# EasyEDA_ATTinyX5_Programmer_V1_Schematic.net
KiCad netlist of a schematic drawn in EasyEDA
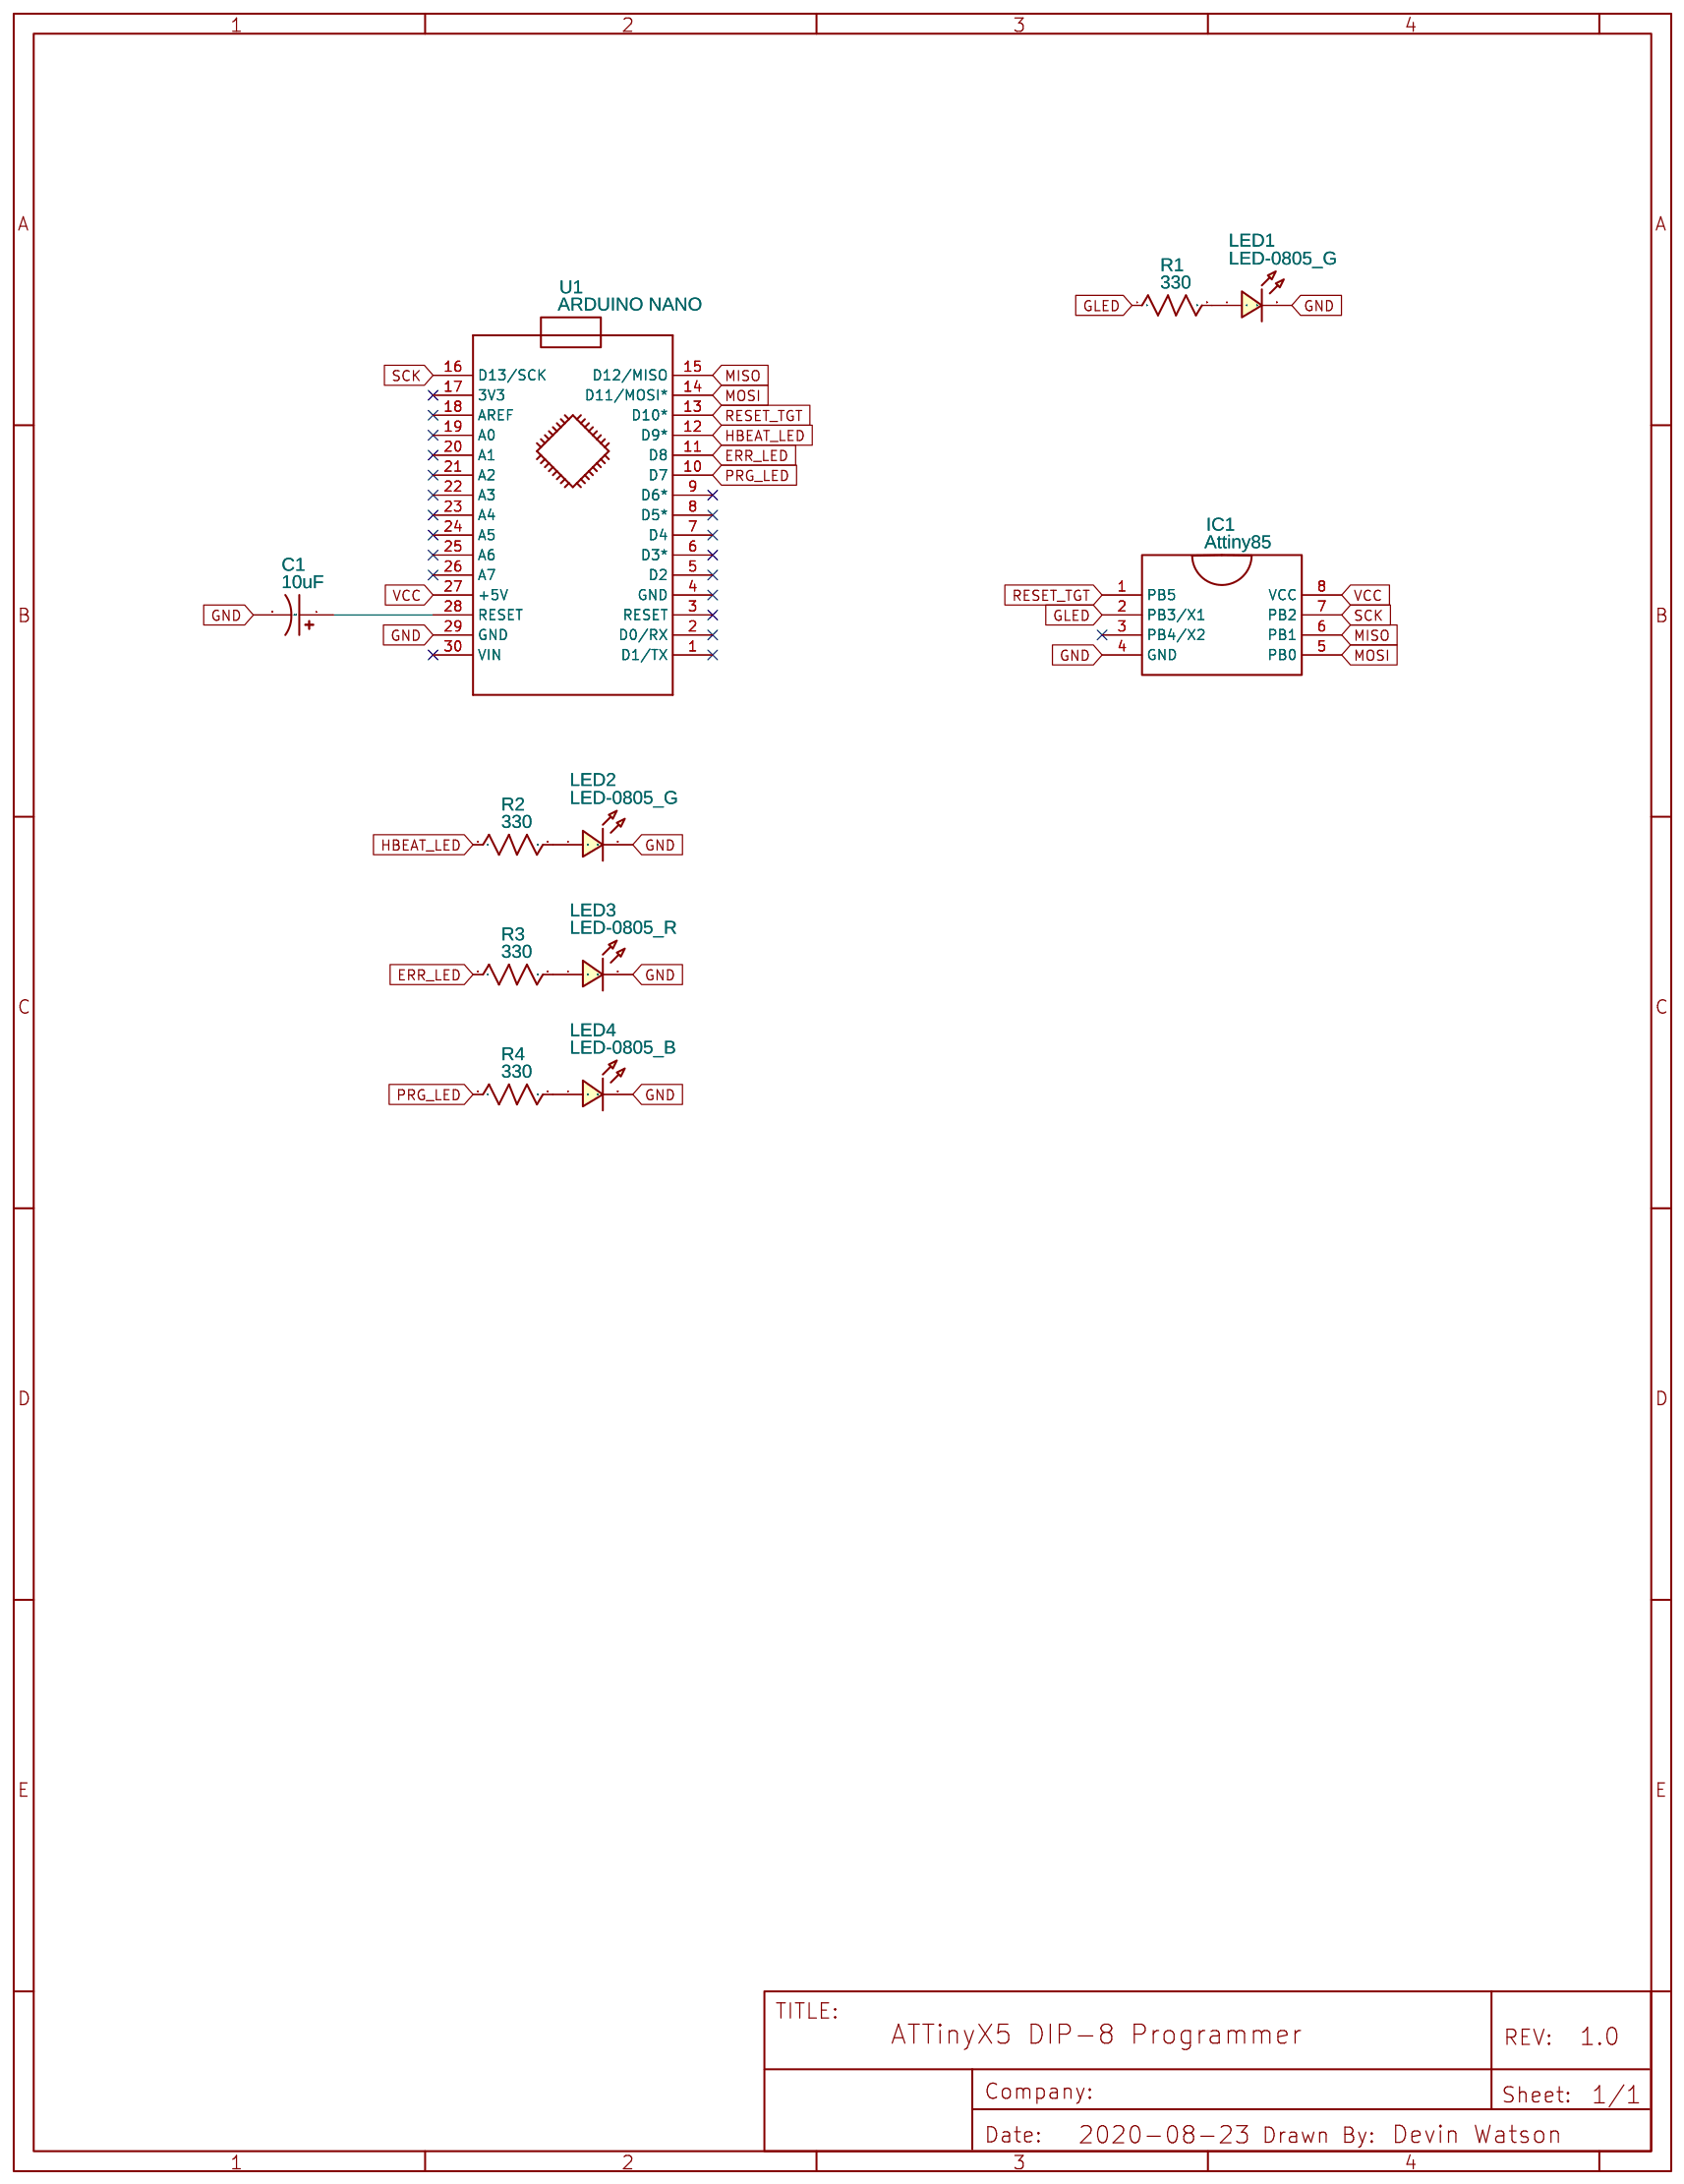
[diagram p0: schematic sheet]

(export (version "E")
  (design (tool "Eeschema 10.0.6"))
  (components
    (comp (ref "C1")
      (value "10uF")
      (fields
        (field (name "BOM_Manufacturer Part") "EEE-HP0J100R")
        (field (name "BOM_Supplier Part") "667-EEE-HP0J100R")
      )
      (libsource (lib "") (part "CE_SMD_D4.0×H5.5_US"))
    )
    (comp (ref "IC1") (value "Attiny85") (libsource (lib "") (part "Attiny85")))
    (comp (ref "LED1")
      (value "LED-0805_G")
      (fields
        (field (name "BOM_Manufacturer Part") "17-21SYGC/S530-E2/TR8")
        (field (name "BOM_Supplier Part") "638-1721SYGCS530E2")
      )
      (libsource (lib "") (part "LED-0805_G"))
    )
    (comp (ref "LED2")
      (value "LED-0805_G")
      (fields
        (field (name "BOM_Manufacturer Part") "17-21SYGC/S530-E2/TR8")
        (field (name "BOM_Supplier Part") "638-1721SYGCS530E2")
      )
      (libsource (lib "") (part "LED-0805_G"))
    )
    (comp (ref "LED3")
      (value "LED-0805_R")
      (fields
        (field (name "BOM_Manufacturer Part") "EL-12-215SURC/S530-A2/TR8")
        (field (name "BOM_Supplier Part") "638-215SURCS530A28")
      )
      (libsource (lib "") (part "LED-0805_R"))
    )
    (comp (ref "LED4")
      (value "LED-0805_B")
      (fields
        (field (name "BOM_Manufacturer Part") "LTST-C170TBKT")
        (field (name "BOM_Supplier Part") "859-LTST-C170TBKT")
      )
      (libsource (lib "") (part "LED-0805_B"))
    )
    (comp (ref "R1")
      (value "330")
      (fields
        (field (name "BOM_Manufacturer Part") "CRCW0805330RJNEAC")
        (field (name "BOM_Supplier Part") "71-CRCW0805330RJNEAC")
      )
      (libsource (lib "") (part "R_0805_US"))
    )
    (comp (ref "R2")
      (value "330")
      (fields
        (field (name "BOM_Manufacturer Part") "CRCW0805330RJNEAC")
        (field (name "BOM_Supplier Part") "71-CRCW0805330RJNEAC")
      )
      (libsource (lib "") (part "R_0805_US"))
    )
    (comp (ref "R3")
      (value "330")
      (fields
        (field (name "BOM_Manufacturer Part") "CRCW0805330RJNEAC")
        (field (name "BOM_Supplier Part") "71-CRCW0805330RJNEAC")
      )
      (libsource (lib "") (part "R_0805_US"))
    )
    (comp (ref "R4")
      (value "330")
      (fields
        (field (name "BOM_Manufacturer Part") "CRCW0805330RJNEAC")
        (field (name "BOM_Supplier Part") "71-CRCW0805330RJNEAC")
      )
      (libsource (lib "") (part "R_0805_US"))
    )
    (comp (ref "U1")
      (value "ARDUINO NANO")
      (fields (field (name "BOM_Manufacturer Part") "?"))
      (libsource (lib "") (part "Unknown_280_-560"))
    )
  )
  (nets
    (net (code "1") (name "ERR_LED") (class "Default")
      (node (ref "R3") (pin "1") (pinfunction "1_1") (pintype "unspecified"))
      (node (ref "U1") (pin "11") (pinfunction "D8_11") (pintype "unspecified"))
    )
    (net (code "2") (name "GLED") (class "Default")
      (node (ref "IC1") (pin "2") (pinfunction "PB3/X1_2") (pintype "bidirectional"))
      (node (ref "R1") (pin "1") (pinfunction "1_1") (pintype "unspecified"))
    )
    (net (code "3") (name "GND") (class "Default")
      (node (ref "C1") (pin "2") (pinfunction "2_2") (pintype "unspecified"))
      (node (ref "IC1") (pin "4") (pinfunction "GND_4") (pintype "passive"))
      (node (ref "LED1") (pin "2") (pinfunction "2_2") (pintype "unspecified"))
      (node (ref "LED2") (pin "2") (pinfunction "2_2") (pintype "unspecified"))
      (node (ref "LED3") (pin "2") (pinfunction "2_2") (pintype "unspecified"))
      (node (ref "LED4") (pin "2") (pinfunction "2_2") (pintype "unspecified"))
      (node (ref "U1") (pin "29") (pinfunction "GND_29") (pintype "unspecified"))
    )
    (net (code "4") (name "HBEAT_LED") (class "Default")
      (node (ref "R2") (pin "1") (pinfunction "1_1") (pintype "unspecified"))
      (node (ref "U1") (pin "12") (pinfunction "D9*_12") (pintype "unspecified"))
    )
    (net (code "5") (name "MISO") (class "Default")
      (node (ref "IC1") (pin "6") (pinfunction "PB1_6") (pintype "bidirectional"))
      (node (ref "U1") (pin "15") (pinfunction "D12/MISO_15") (pintype "unspecified"))
    )
    (net (code "6") (name "MOSI") (class "Default")
      (node (ref "IC1") (pin "5") (pinfunction "PB0_5") (pintype "bidirectional"))
      (node (ref "U1") (pin "14") (pinfunction "D11/MOSI*_14") (pintype "unspecified"))
    )
    (net (code "7") (name "Net-(C1-Pad1)") (class "Default")
      (node (ref "C1") (pin "1") (pinfunction "1_1") (pintype "unspecified"))
      (node (ref "U1") (pin "28") (pinfunction "RESET_28") (pintype "unspecified"))
    )
    (net (code "8") (name "Net-(LED1-Pad1)") (class "Default")
      (node (ref "LED1") (pin "1") (pinfunction "1_1") (pintype "unspecified"))
      (node (ref "R1") (pin "2") (pinfunction "2_2") (pintype "unspecified"))
    )
    (net (code "9") (name "Net-(LED2-Pad1)") (class "Default")
      (node (ref "LED2") (pin "1") (pinfunction "1_1") (pintype "unspecified"))
      (node (ref "R2") (pin "2") (pinfunction "2_2") (pintype "unspecified"))
    )
    (net (code "10") (name "Net-(LED3-Pad1)") (class "Default")
      (node (ref "LED3") (pin "1") (pinfunction "1_1") (pintype "unspecified"))
      (node (ref "R3") (pin "2") (pinfunction "2_2") (pintype "unspecified"))
    )
    (net (code "11") (name "Net-(LED4-Pad1)") (class "Default")
      (node (ref "LED4") (pin "1") (pinfunction "1_1") (pintype "unspecified"))
      (node (ref "R4") (pin "2") (pinfunction "2_2") (pintype "unspecified"))
    )
    (net (code "12") (name "PRG_LED") (class "Default")
      (node (ref "R4") (pin "1") (pinfunction "1_1") (pintype "unspecified"))
      (node (ref "U1") (pin "10") (pinfunction "D7_10") (pintype "unspecified"))
    )
    (net (code "13") (name "RESET_TGT") (class "Default")
      (node (ref "IC1") (pin "1") (pinfunction "PB5_1") (pintype "bidirectional"))
      (node (ref "U1") (pin "13") (pinfunction "D10*_13") (pintype "unspecified"))
    )
    (net (code "14") (name "SCK") (class "Default")
      (node (ref "IC1") (pin "7") (pinfunction "PB2_7") (pintype "bidirectional"))
      (node (ref "U1") (pin "16") (pinfunction "D13/SCK_16") (pintype "unspecified"))
    )
    (net (code "15") (name "VCC") (class "Default")
      (node (ref "IC1") (pin "8") (pinfunction "VCC_8") (pintype "passive"))
      (node (ref "U1") (pin "27") (pinfunction "+5V_27") (pintype "unspecified"))
    )
    (net (code "16") (name "unconnected-(IC1-PB4{slash}X2-Pad3)") (class "Default")
      (node (ref "IC1") (pin "3") (pinfunction "PB4/X2_3") (pintype "bidirectional+no_connect"))
    )
    (net (code "17") (name "unconnected-(U1-3V3-Pad17)") (class "Default")
      (node (ref "U1") (pin "17") (pinfunction "3V3_17") (pintype "unspecified+no_connect"))
    )
    (net (code "18") (name "unconnected-(U1-A0-Pad19)") (class "Default")
      (node (ref "U1") (pin "19") (pinfunction "A0_19") (pintype "unspecified+no_connect"))
    )
    (net (code "19") (name "unconnected-(U1-A1-Pad20)") (class "Default")
      (node (ref "U1") (pin "20") (pinfunction "A1_20") (pintype "unspecified+no_connect"))
    )
    (net (code "20") (name "unconnected-(U1-A2-Pad21)") (class "Default")
      (node (ref "U1") (pin "21") (pinfunction "A2_21") (pintype "unspecified+no_connect"))
    )
    (net (code "21") (name "unconnected-(U1-A3-Pad22)") (class "Default")
      (node (ref "U1") (pin "22") (pinfunction "A3_22") (pintype "unspecified+no_connect"))
    )
    (net (code "22") (name "unconnected-(U1-A4-Pad23)") (class "Default")
      (node (ref "U1") (pin "23") (pinfunction "A4_23") (pintype "unspecified+no_connect"))
    )
    (net (code "23") (name "unconnected-(U1-A5-Pad24)") (class "Default")
      (node (ref "U1") (pin "24") (pinfunction "A5_24") (pintype "unspecified+no_connect"))
    )
    (net (code "24") (name "unconnected-(U1-A6-Pad25)") (class "Default")
      (node (ref "U1") (pin "25") (pinfunction "A6_25") (pintype "unspecified+no_connect"))
    )
    (net (code "25") (name "unconnected-(U1-A7-Pad26)") (class "Default")
      (node (ref "U1") (pin "26") (pinfunction "A7_26") (pintype "unspecified+no_connect"))
    )
    (net (code "26") (name "unconnected-(U1-AREF-Pad18)") (class "Default")
      (node (ref "U1") (pin "18") (pinfunction "AREF_18") (pintype "unspecified+no_connect"))
    )
    (net (code "27") (name "unconnected-(U1-D0{slash}RX-Pad2)") (class "Default")
      (node (ref "U1") (pin "2") (pinfunction "D0/RX_2") (pintype "unspecified+no_connect"))
    )
    (net (code "28") (name "unconnected-(U1-D1{slash}TX-Pad1)") (class "Default")
      (node (ref "U1") (pin "1") (pinfunction "D1/TX_1") (pintype "unspecified+no_connect"))
    )
    (net (code "29") (name "unconnected-(U1-D2-Pad5)") (class "Default")
      (node (ref "U1") (pin "5") (pinfunction "D2_5") (pintype "unspecified+no_connect"))
    )
    (net (code "30") (name "unconnected-(U1-D3*-Pad6)") (class "Default")
      (node (ref "U1") (pin "6") (pinfunction "D3*_6") (pintype "unspecified+no_connect"))
    )
    (net (code "31") (name "unconnected-(U1-D4-Pad7)") (class "Default")
      (node (ref "U1") (pin "7") (pinfunction "D4_7") (pintype "unspecified+no_connect"))
    )
    (net (code "32") (name "unconnected-(U1-D5*-Pad8)") (class "Default")
      (node (ref "U1") (pin "8") (pinfunction "D5*_8") (pintype "unspecified+no_connect"))
    )
    (net (code "33") (name "unconnected-(U1-D6*-Pad9)") (class "Default")
      (node (ref "U1") (pin "9") (pinfunction "D6*_9") (pintype "unspecified+no_connect"))
    )
    (net (code "34") (name "unconnected-(U1-GND-Pad4)") (class "Default")
      (node (ref "U1") (pin "4") (pinfunction "GND_4") (pintype "unspecified+no_connect"))
    )
    (net (code "35") (name "unconnected-(U1-RESET-Pad3)") (class "Default")
      (node (ref "U1") (pin "3") (pinfunction "RESET_3") (pintype "unspecified+no_connect"))
    )
    (net (code "36") (name "unconnected-(U1-VIN-Pad30)") (class "Default")
      (node (ref "U1") (pin "30") (pinfunction "VIN_30") (pintype "unspecified+no_connect"))
    )
  )
)
